# SAOP.net
KiCad netlist of a schematic drawn in EAGLE
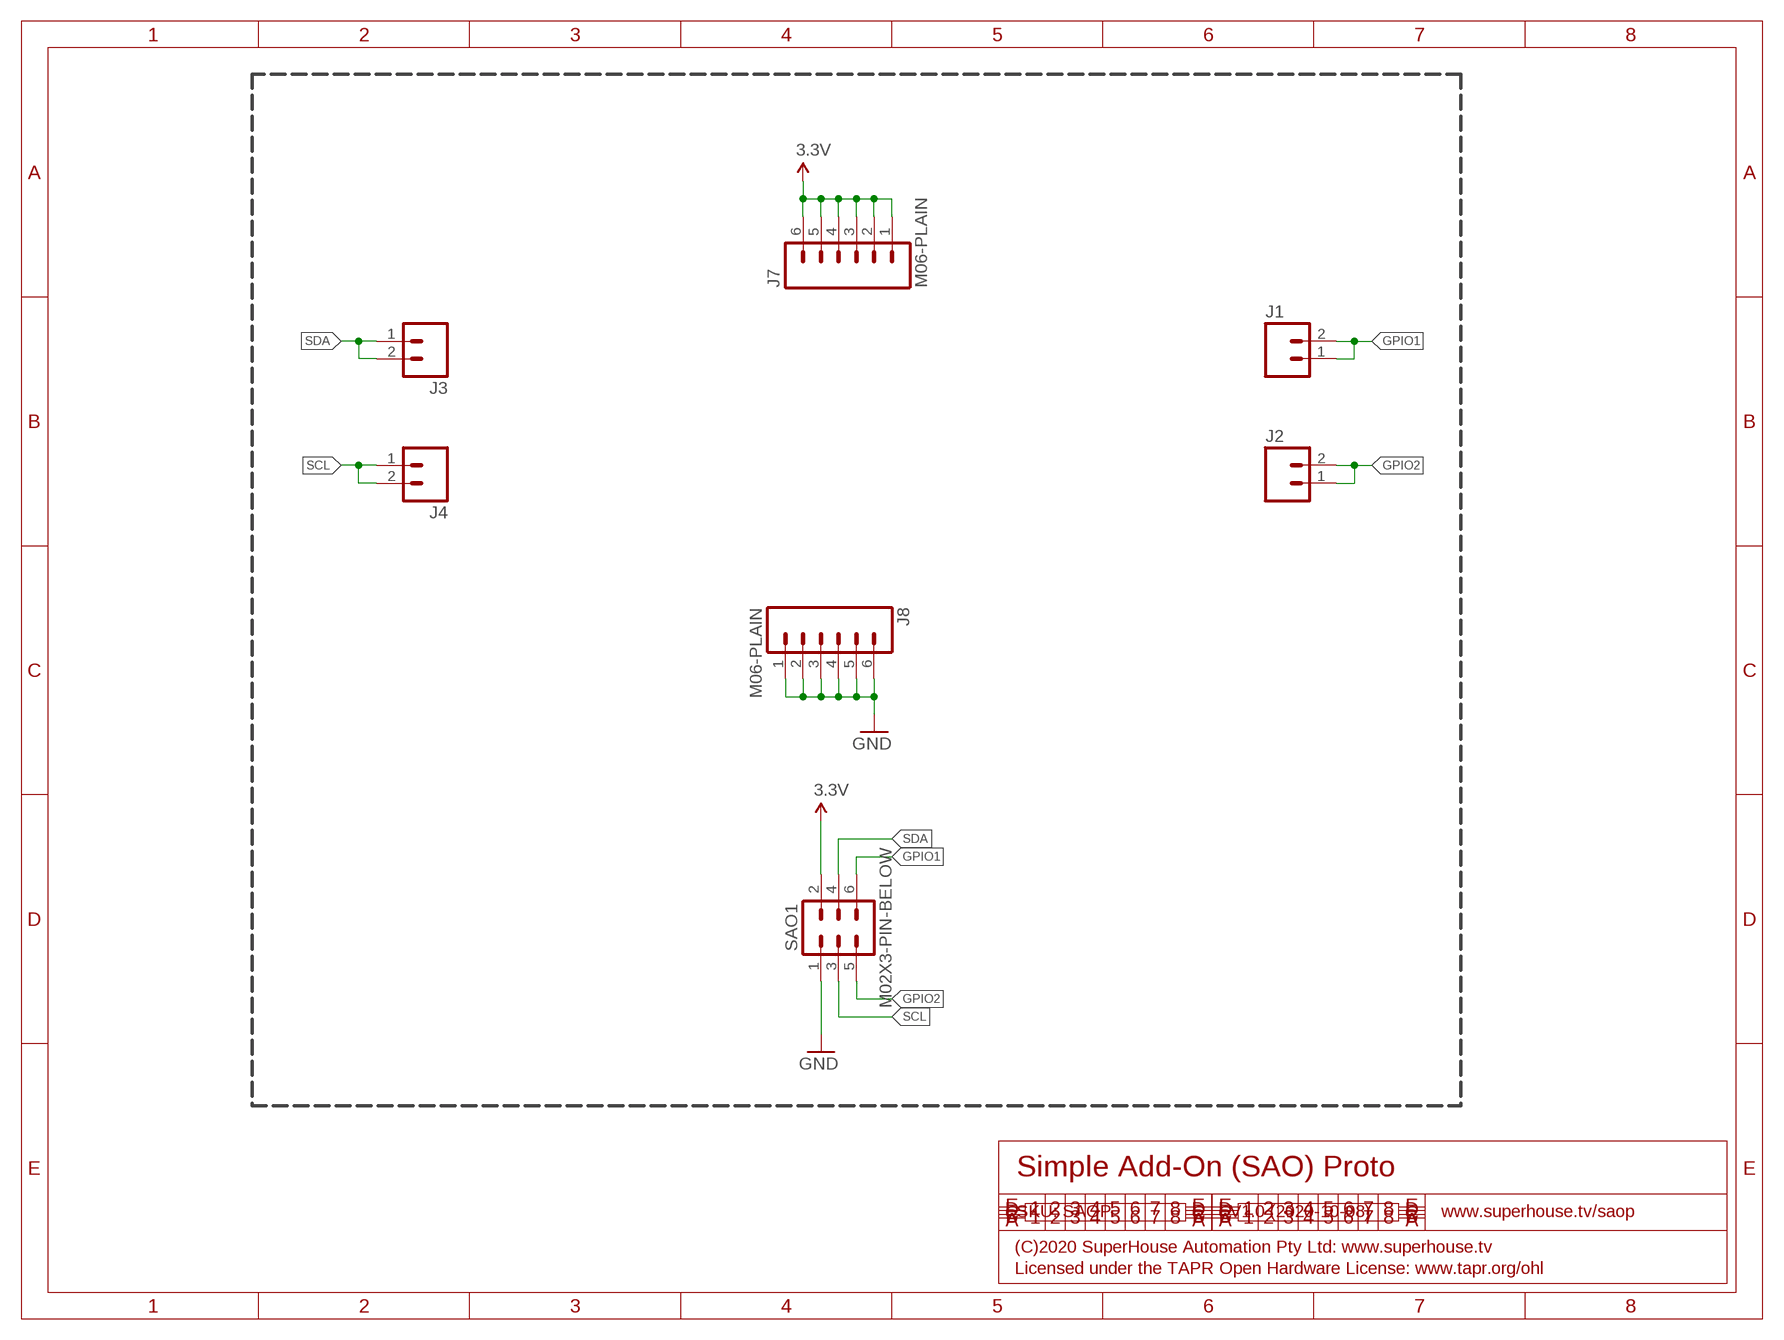
[diagram p0: schematic, sheet 1]

(export (version "E")
  (design (tool "Eeschema 10.0.6"))
  (components
    (comp (ref "J1")
      (value "M02-PLAIN")
      (footprint "eagle-import:1X02")
      (libsource (lib "eagle-import") (part "M02-PLAIN"))
    )
    (comp (ref "J2")
      (value "M02-PLAIN")
      (footprint "eagle-import:1X02")
      (libsource (lib "eagle-import") (part "M02-PLAIN"))
    )
    (comp (ref "J3")
      (value "M02-PLAIN")
      (footprint "eagle-import:1X02")
      (libsource (lib "eagle-import") (part "M02-PLAIN"))
    )
    (comp (ref "J4")
      (value "M02-PLAIN")
      (footprint "eagle-import:1X02")
      (libsource (lib "eagle-import") (part "M02-PLAIN"))
    )
    (comp (ref "J7")
      (value "M06-PLAIN")
      (footprint "eagle-import:1X06")
      (libsource (lib "eagle-import") (part "M06-PLAIN"))
    )
    (comp (ref "J8")
      (value "M06-PLAIN")
      (footprint "eagle-import:1X06")
      (libsource (lib "eagle-import") (part "M06-PLAIN"))
    )
    (comp (ref "SAO1")
      (value "M02X3-PIN-BELOW")
      (footprint "eagle-import:2X03-P-BELOW")
      (libsource (lib "eagle-import") (part "M02X3-PIN-BELOW"))
    )
  )
  (nets
    (net (code "1") (name "3.3V") (class "Default")
      (node (ref "J7") (pin "1") (pinfunction "1_1") (pintype "passive"))
      (node (ref "J7") (pin "2") (pinfunction "2_2") (pintype "passive"))
      (node (ref "J7") (pin "3") (pinfunction "3_3") (pintype "passive"))
      (node (ref "J7") (pin "4") (pinfunction "4_4") (pintype "passive"))
      (node (ref "J7") (pin "5") (pinfunction "5_5") (pintype "passive"))
      (node (ref "J7") (pin "6") (pinfunction "6_6") (pintype "passive"))
      (node (ref "SAO1") (pin "2") (pinfunction "2_2") (pintype "passive"))
    )
    (net (code "2") (name "GND") (class "Default")
      (node (ref "J8") (pin "1") (pinfunction "1_1") (pintype "passive"))
      (node (ref "J8") (pin "2") (pinfunction "2_2") (pintype "passive"))
      (node (ref "J8") (pin "3") (pinfunction "3_3") (pintype "passive"))
      (node (ref "J8") (pin "4") (pinfunction "4_4") (pintype "passive"))
      (node (ref "J8") (pin "5") (pinfunction "5_5") (pintype "passive"))
      (node (ref "J8") (pin "6") (pinfunction "6_6") (pintype "passive"))
      (node (ref "SAO1") (pin "1") (pinfunction "1_1") (pintype "passive"))
    )
    (net (code "3") (name "GPIO1") (class "Default")
      (node (ref "J1") (pin "1") (pinfunction "1_1") (pintype "passive"))
      (node (ref "J1") (pin "2") (pinfunction "2_2") (pintype "passive"))
      (node (ref "SAO1") (pin "6") (pinfunction "6_6") (pintype "passive"))
    )
    (net (code "4") (name "GPIO2") (class "Default")
      (node (ref "J2") (pin "1") (pinfunction "1_1") (pintype "passive"))
      (node (ref "J2") (pin "2") (pinfunction "2_2") (pintype "passive"))
      (node (ref "SAO1") (pin "5") (pinfunction "5_5") (pintype "passive"))
    )
    (net (code "5") (name "SCL") (class "Default")
      (node (ref "J4") (pin "1") (pinfunction "1_1") (pintype "passive"))
      (node (ref "J4") (pin "2") (pinfunction "2_2") (pintype "passive"))
      (node (ref "SAO1") (pin "3") (pinfunction "3_3") (pintype "passive"))
    )
    (net (code "6") (name "SDA") (class "Default")
      (node (ref "J3") (pin "1") (pinfunction "1_1") (pintype "passive"))
      (node (ref "J3") (pin "2") (pinfunction "2_2") (pintype "passive"))
      (node (ref "SAO1") (pin "4") (pinfunction "4_4") (pintype "passive"))
    )
  )
)
